# pikeyboard-56SWD2.net
KiCad netlist of a schematic drawn in EAGLE
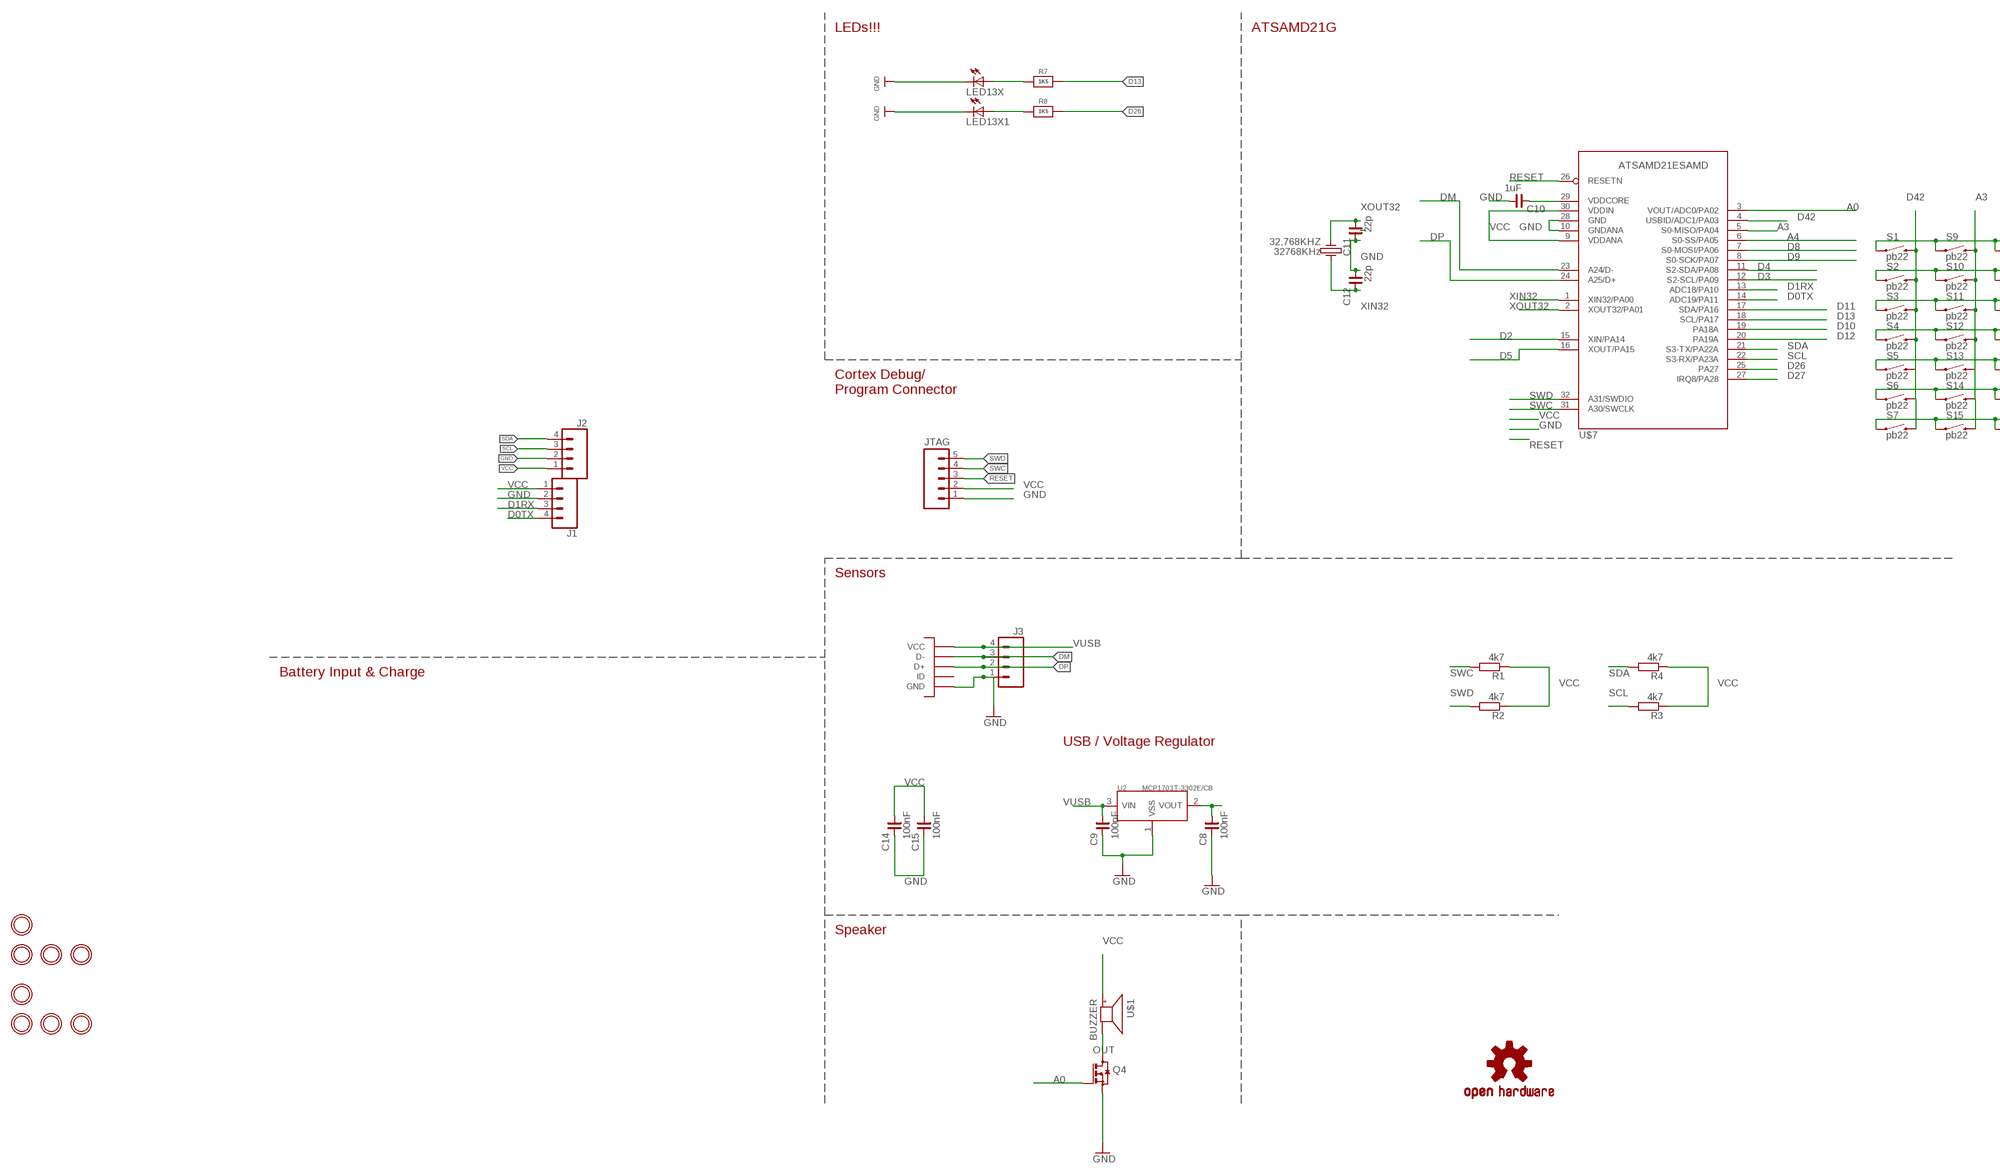
[diagram p0: schematic, sheet 1, part 1 of 2]
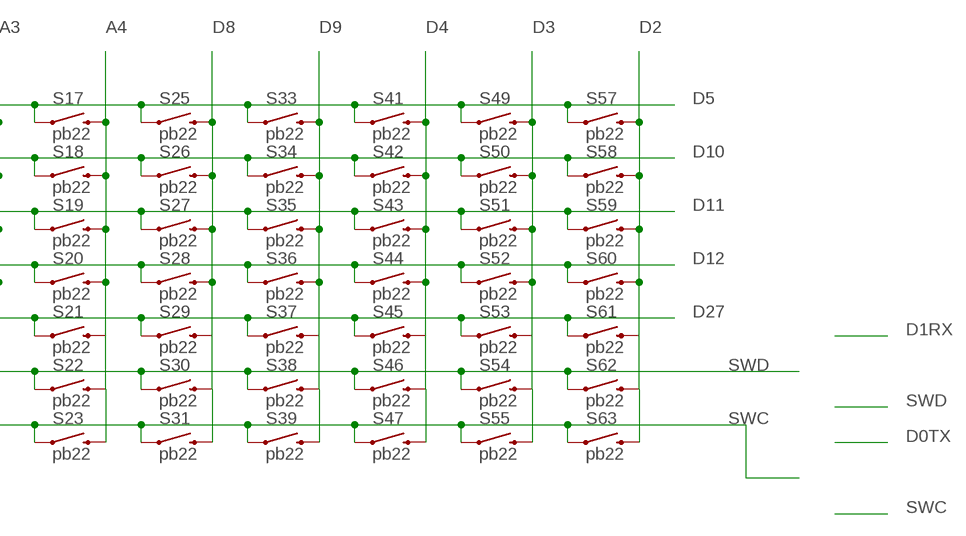
[diagram p1: schematic, sheet 1, part 2 of 2]

(export (version "E")
  (design (tool "Eeschema 10.0.6"))
  (components
    (comp (ref "32,768KHZ")
      (value "32768KHz")
      (footprint "eagle-import:KX-327LT")
      (libsource (lib "eagle-import") (part "CRYSTALL"))
    )
    (comp (ref "C8")
      (value "100nF")
      (footprint "eagle-import:C0603")
      (libsource (lib "eagle-import") (part "C_0603"))
    )
    (comp (ref "C9")
      (value "100nF")
      (footprint "eagle-import:C0603")
      (libsource (lib "eagle-import") (part "C_0603"))
    )
    (comp (ref "C10")
      (value "1uF")
      (footprint "eagle-import:C0603")
      (libsource (lib "eagle-import") (part "C_0603"))
    )
    (comp (ref "C11")
      (value "22p")
      (footprint "eagle-import:C0603")
      (libsource (lib "eagle-import") (part "C_0603"))
    )
    (comp (ref "C12")
      (value "22p")
      (footprint "eagle-import:C0603")
      (libsource (lib "eagle-import") (part "C_0603"))
    )
    (comp (ref "C14")
      (value "100nF")
      (footprint "eagle-import:C0603")
      (libsource (lib "eagle-import") (part "C_0603"))
    )
    (comp (ref "C15")
      (value "100nF")
      (footprint "eagle-import:C0603")
      (libsource (lib "eagle-import") (part "C_0603"))
    )
    (comp (ref "J1")
      (value "CONN_041X04_NO_SILK")
      (footprint "eagle-import:1X04_NO_SILK")
      (libsource (lib "eagle-import") (part "CONN_041X04_NO_SILK"))
    )
    (comp (ref "J2")
      (value "CONN_041X04_NO_SILK")
      (footprint "eagle-import:1X04_NO_SILK")
      (libsource (lib "eagle-import") (part "CONN_041X04_NO_SILK"))
    )
    (comp (ref "J3")
      (value "CONN_041.27MM")
      (footprint "eagle-import:1X04_1.27MM")
      (libsource (lib "eagle-import") (part "CONN_041.27MM"))
    )
    (comp (ref "JTAG")
      (value "M051.27MM")
      (footprint "eagle-import:1X05-1.27MM")
      (libsource (lib "eagle-import") (part "M051.27MM"))
    )
    (comp (ref "LED13X")
      (value "LED3MM")
      (footprint "eagle-import:LED3MM")
      (libsource (lib "eagle-import") (part "LED3MM"))
    )
    (comp (ref "LED13X1")
      (value "LED3MM")
      (footprint "eagle-import:LED3MM")
      (libsource (lib "eagle-import") (part "LED3MM"))
    )
    (comp (ref "LOGO3")
      (value "OSHW-LOGOS")
      (footprint "eagle-import:OSHW-LOGO-S")
      (libsource (lib "eagle-import") (part "OSHW-LOGOS"))
    )
    (comp (ref "Q4")
      (value "BSS123")
      (footprint "eagle-import:SOT23")
      (libsource (lib "eagle-import") (part "BSS123"))
    )
    (comp (ref "R1")
      (value "4k7")
      (footprint "eagle-import:R0603")
      (libsource (lib "eagle-import") (part "R-EU_R0603"))
    )
    (comp (ref "R2")
      (value "4k7")
      (footprint "eagle-import:R0603")
      (libsource (lib "eagle-import") (part "R-EU_R0603"))
    )
    (comp (ref "R3")
      (value "4k7")
      (footprint "eagle-import:R0603")
      (libsource (lib "eagle-import") (part "R-EU_R0603"))
    )
    (comp (ref "R4")
      (value "4k7")
      (footprint "eagle-import:R0603")
      (libsource (lib "eagle-import") (part "R-EU_R0603"))
    )
    (comp (ref "R7")
      (value "1K5")
      (footprint "eagle-import:0603-NO")
      (libsource (lib "eagle-import") (part "RESISTOR_0603_NOOUT"))
    )
    (comp (ref "R8")
      (value "1K5")
      (footprint "eagle-import:0603-NO")
      (libsource (lib "eagle-import") (part "RESISTOR_0603_NOOUT"))
    )
    (comp (ref "S1")
      (value "pb22")
      (footprint "eagle-import:TACTILE-PTH")
      (libsource (lib "eagle-import") (part "SWITCH-MOMENTARY-2PTH"))
    )
    (comp (ref "S2")
      (value "pb22")
      (footprint "eagle-import:TACTILE-PTH")
      (libsource (lib "eagle-import") (part "SWITCH-MOMENTARY-2PTH"))
    )
    (comp (ref "S3")
      (value "pb22")
      (footprint "eagle-import:TACTILE-PTH")
      (libsource (lib "eagle-import") (part "SWITCH-MOMENTARY-2PTH"))
    )
    (comp (ref "S4")
      (value "pb22")
      (footprint "eagle-import:TACTILE-PTH")
      (libsource (lib "eagle-import") (part "SWITCH-MOMENTARY-2PTH"))
    )
    (comp (ref "S5")
      (value "pb22")
      (footprint "eagle-import:TACTILE-PTH")
      (libsource (lib "eagle-import") (part "SWITCH-MOMENTARY-2PTH"))
    )
    (comp (ref "S6")
      (value "pb22")
      (footprint "eagle-import:TACTILE-PTH")
      (libsource (lib "eagle-import") (part "SWITCH-MOMENTARY-2PTH"))
    )
    (comp (ref "S7")
      (value "pb22")
      (footprint "eagle-import:TACTILE-PTH")
      (libsource (lib "eagle-import") (part "SWITCH-MOMENTARY-2PTH"))
    )
    (comp (ref "S9")
      (value "pb22")
      (footprint "eagle-import:TACTILE-PTH")
      (libsource (lib "eagle-import") (part "SWITCH-MOMENTARY-2PTH"))
    )
    (comp (ref "S10")
      (value "pb22")
      (footprint "eagle-import:TACTILE-PTH")
      (libsource (lib "eagle-import") (part "SWITCH-MOMENTARY-2PTH"))
    )
    (comp (ref "S11")
      (value "pb22")
      (footprint "eagle-import:TACTILE-PTH")
      (libsource (lib "eagle-import") (part "SWITCH-MOMENTARY-2PTH"))
    )
    (comp (ref "S12")
      (value "pb22")
      (footprint "eagle-import:TACTILE-PTH")
      (libsource (lib "eagle-import") (part "SWITCH-MOMENTARY-2PTH"))
    )
    (comp (ref "S13")
      (value "pb22")
      (footprint "eagle-import:TACTILE-PTH")
      (libsource (lib "eagle-import") (part "SWITCH-MOMENTARY-2PTH"))
    )
    (comp (ref "S14")
      (value "pb22")
      (footprint "eagle-import:TACTILE-PTH")
      (libsource (lib "eagle-import") (part "SWITCH-MOMENTARY-2PTH"))
    )
    (comp (ref "S15")
      (value "pb22")
      (footprint "eagle-import:TACTILE-PTH")
      (libsource (lib "eagle-import") (part "SWITCH-MOMENTARY-2PTH"))
    )
    (comp (ref "S17")
      (value "pb22")
      (footprint "eagle-import:TACTILE-PTH")
      (libsource (lib "eagle-import") (part "SWITCH-MOMENTARY-2PTH"))
    )
    (comp (ref "S18")
      (value "pb22")
      (footprint "eagle-import:TACTILE-PTH")
      (libsource (lib "eagle-import") (part "SWITCH-MOMENTARY-2PTH"))
    )
    (comp (ref "S19")
      (value "pb22")
      (footprint "eagle-import:TACTILE-PTH")
      (libsource (lib "eagle-import") (part "SWITCH-MOMENTARY-2PTH"))
    )
    (comp (ref "S20")
      (value "pb22")
      (footprint "eagle-import:TACTILE-PTH")
      (libsource (lib "eagle-import") (part "SWITCH-MOMENTARY-2PTH"))
    )
    (comp (ref "S21")
      (value "pb22")
      (footprint "eagle-import:TACTILE-PTH")
      (libsource (lib "eagle-import") (part "SWITCH-MOMENTARY-2PTH"))
    )
    (comp (ref "S22")
      (value "pb22")
      (footprint "eagle-import:TACTILE-PTH")
      (libsource (lib "eagle-import") (part "SWITCH-MOMENTARY-2PTH"))
    )
    (comp (ref "S23")
      (value "pb22")
      (footprint "eagle-import:TACTILE-PTH")
      (libsource (lib "eagle-import") (part "SWITCH-MOMENTARY-2PTH"))
    )
    (comp (ref "S25")
      (value "pb22")
      (footprint "eagle-import:TACTILE-PTH")
      (libsource (lib "eagle-import") (part "SWITCH-MOMENTARY-2PTH"))
    )
    (comp (ref "S26")
      (value "pb22")
      (footprint "eagle-import:TACTILE-PTH")
      (libsource (lib "eagle-import") (part "SWITCH-MOMENTARY-2PTH"))
    )
    (comp (ref "S27")
      (value "pb22")
      (footprint "eagle-import:TACTILE-PTH")
      (libsource (lib "eagle-import") (part "SWITCH-MOMENTARY-2PTH"))
    )
    (comp (ref "S28")
      (value "pb22")
      (footprint "eagle-import:TACTILE-PTH")
      (libsource (lib "eagle-import") (part "SWITCH-MOMENTARY-2PTH"))
    )
    (comp (ref "S29")
      (value "pb22")
      (footprint "eagle-import:TACTILE-PTH")
      (libsource (lib "eagle-import") (part "SWITCH-MOMENTARY-2PTH"))
    )
    (comp (ref "S30")
      (value "pb22")
      (footprint "eagle-import:TACTILE-PTH")
      (libsource (lib "eagle-import") (part "SWITCH-MOMENTARY-2PTH"))
    )
    (comp (ref "S31")
      (value "pb22")
      (footprint "eagle-import:TACTILE-PTH")
      (libsource (lib "eagle-import") (part "SWITCH-MOMENTARY-2PTH"))
    )
    (comp (ref "S33")
      (value "pb22")
      (footprint "eagle-import:TACTILE-PTH")
      (libsource (lib "eagle-import") (part "SWITCH-MOMENTARY-2PTH"))
    )
    (comp (ref "S34")
      (value "pb22")
      (footprint "eagle-import:TACTILE-PTH")
      (libsource (lib "eagle-import") (part "SWITCH-MOMENTARY-2PTH"))
    )
    (comp (ref "S35")
      (value "pb22")
      (footprint "eagle-import:TACTILE-PTH")
      (libsource (lib "eagle-import") (part "SWITCH-MOMENTARY-2PTH"))
    )
    (comp (ref "S36")
      (value "pb22")
      (footprint "eagle-import:TACTILE-PTH")
      (libsource (lib "eagle-import") (part "SWITCH-MOMENTARY-2PTH"))
    )
    (comp (ref "S37")
      (value "pb22")
      (footprint "eagle-import:TACTILE-PTH")
      (libsource (lib "eagle-import") (part "SWITCH-MOMENTARY-2PTH"))
    )
    (comp (ref "S38")
      (value "pb22")
      (footprint "eagle-import:TACTILE-PTH")
      (libsource (lib "eagle-import") (part "SWITCH-MOMENTARY-2PTH"))
    )
    (comp (ref "S39")
      (value "pb22")
      (footprint "eagle-import:TACTILE-PTH")
      (libsource (lib "eagle-import") (part "SWITCH-MOMENTARY-2PTH"))
    )
    (comp (ref "S41")
      (value "pb22")
      (footprint "eagle-import:TACTILE-PTH")
      (libsource (lib "eagle-import") (part "SWITCH-MOMENTARY-2PTH"))
    )
    (comp (ref "S42")
      (value "pb22")
      (footprint "eagle-import:TACTILE-PTH")
      (libsource (lib "eagle-import") (part "SWITCH-MOMENTARY-2PTH"))
    )
    (comp (ref "S43")
      (value "pb22")
      (footprint "eagle-import:TACTILE-PTH")
      (libsource (lib "eagle-import") (part "SWITCH-MOMENTARY-2PTH"))
    )
    (comp (ref "S44")
      (value "pb22")
      (footprint "eagle-import:TACTILE-PTH")
      (libsource (lib "eagle-import") (part "SWITCH-MOMENTARY-2PTH"))
    )
    (comp (ref "S45")
      (value "pb22")
      (footprint "eagle-import:TACTILE-PTH")
      (libsource (lib "eagle-import") (part "SWITCH-MOMENTARY-2PTH"))
    )
    (comp (ref "S46")
      (value "pb22")
      (footprint "eagle-import:TACTILE-PTH")
      (libsource (lib "eagle-import") (part "SWITCH-MOMENTARY-2PTH"))
    )
    (comp (ref "S47")
      (value "pb22")
      (footprint "eagle-import:TACTILE-PTH")
      (libsource (lib "eagle-import") (part "SWITCH-MOMENTARY-2PTH"))
    )
    (comp (ref "S49")
      (value "pb22")
      (footprint "eagle-import:TACTILE-PTH")
      (libsource (lib "eagle-import") (part "SWITCH-MOMENTARY-2PTH"))
    )
    (comp (ref "S50")
      (value "pb22")
      (footprint "eagle-import:TACTILE-PTH")
      (libsource (lib "eagle-import") (part "SWITCH-MOMENTARY-2PTH"))
    )
    (comp (ref "S51")
      (value "pb22")
      (footprint "eagle-import:TACTILE-PTH")
      (libsource (lib "eagle-import") (part "SWITCH-MOMENTARY-2PTH"))
    )
    (comp (ref "S52")
      (value "pb22")
      (footprint "eagle-import:TACTILE-PTH")
      (libsource (lib "eagle-import") (part "SWITCH-MOMENTARY-2PTH"))
    )
    (comp (ref "S53")
      (value "pb22")
      (footprint "eagle-import:TACTILE-PTH")
      (libsource (lib "eagle-import") (part "SWITCH-MOMENTARY-2PTH"))
    )
    (comp (ref "S54")
      (value "pb22")
      (footprint "eagle-import:TACTILE-PTH")
      (libsource (lib "eagle-import") (part "SWITCH-MOMENTARY-2PTH"))
    )
    (comp (ref "S55")
      (value "pb22")
      (footprint "eagle-import:TACTILE-PTH")
      (libsource (lib "eagle-import") (part "SWITCH-MOMENTARY-2PTH"))
    )
    (comp (ref "S57")
      (value "pb22")
      (footprint "eagle-import:TACTILE-PTH")
      (libsource (lib "eagle-import") (part "SWITCH-MOMENTARY-2PTH"))
    )
    (comp (ref "S58")
      (value "pb22")
      (footprint "eagle-import:TACTILE-PTH")
      (libsource (lib "eagle-import") (part "SWITCH-MOMENTARY-2PTH"))
    )
    (comp (ref "S59")
      (value "pb22")
      (footprint "eagle-import:TACTILE-PTH")
      (libsource (lib "eagle-import") (part "SWITCH-MOMENTARY-2PTH"))
    )
    (comp (ref "S60")
      (value "pb22")
      (footprint "eagle-import:TACTILE-PTH")
      (libsource (lib "eagle-import") (part "SWITCH-MOMENTARY-2PTH"))
    )
    (comp (ref "S61")
      (value "pb22")
      (footprint "eagle-import:TACTILE-PTH")
      (libsource (lib "eagle-import") (part "SWITCH-MOMENTARY-2PTH"))
    )
    (comp (ref "S62")
      (value "pb22")
      (footprint "eagle-import:TACTILE-PTH")
      (libsource (lib "eagle-import") (part "SWITCH-MOMENTARY-2PTH"))
    )
    (comp (ref "S63")
      (value "pb22")
      (footprint "eagle-import:TACTILE-PTH")
      (libsource (lib "eagle-import") (part "SWITCH-MOMENTARY-2PTH"))
    )
    (comp (ref "U$1")
      (value "BUZZER")
      (footprint "eagle-import:SMT-8585-BUZZER")
      (libsource (lib "eagle-import") (part "BUZZER"))
    )
    (comp (ref "U$2")
      (value "MOUNTINGHOLE2.0")
      (footprint "eagle-import:MOUNTINGHOLE_2.0_PLATED")
      (libsource (lib "eagle-import") (part "MOUNTINGHOLE2.0"))
    )
    (comp (ref "U$3")
      (value "MOUNTINGHOLE2.0")
      (footprint "eagle-import:MOUNTINGHOLE_2.0_PLATED")
      (libsource (lib "eagle-import") (part "MOUNTINGHOLE2.0"))
    )
    (comp (ref "U$4")
      (value "MOUNTINGHOLE2.0")
      (footprint "eagle-import:MOUNTINGHOLE_2.0_PLATED")
      (libsource (lib "eagle-import") (part "MOUNTINGHOLE2.0"))
    )
    (comp (ref "U$5")
      (value "MICROUSB")
      (footprint "eagle-import:MICRO_B")
      (libsource (lib "eagle-import") (part "MICROUSB"))
    )
    (comp (ref "U$7")
      (value "ATSAMD21ESAMD")
      (footprint "eagle-import:TQFP32-08")
      (libsource (lib "eagle-import") (part "ATSAMD21ESAMD"))
    )
    (comp (ref "U$8")
      (value "MOUNTINGHOLE2.0")
      (footprint "eagle-import:MOUNTINGHOLE_2.0_PLATED")
      (libsource (lib "eagle-import") (part "MOUNTINGHOLE2.0"))
    )
    (comp (ref "U$10")
      (value "MOUNTINGHOLE2.0")
      (footprint "eagle-import:MOUNTINGHOLE_2.0_PLATED")
      (libsource (lib "eagle-import") (part "MOUNTINGHOLE2.0"))
    )
    (comp (ref "U$11")
      (value "MOUNTINGHOLE2.0")
      (footprint "eagle-import:MOUNTINGHOLE_2.0_PLATED")
      (libsource (lib "eagle-import") (part "MOUNTINGHOLE2.0"))
    )
    (comp (ref "U$12")
      (value "MOUNTINGHOLE2.0")
      (footprint "eagle-import:MOUNTINGHOLE_2.0_PLATED")
      (libsource (lib "eagle-import") (part "MOUNTINGHOLE2.0"))
    )
    (comp (ref "U$13")
      (value "MOUNTINGHOLE2.0")
      (footprint "eagle-import:MOUNTINGHOLE_2.0_PLATED")
      (libsource (lib "eagle-import") (part "MOUNTINGHOLE2.0"))
    )
    (comp (ref "U2")
      (value "MCP1703T-3302E/CB")
      (footprint "eagle-import:SOT23")
      (libsource (lib "eagle-import") (part "XC6206"))
    )
  )
  (nets
    (net (code "1") (name "/A0") (class "Default")
      (node (ref "Q4") (pin "1") (pinfunction "G_1") (pintype "passive"))
      (node (ref "U$7") (pin "3") (pinfunction "VOUT/ADC0/PA02_3") (pintype "bidirectional"))
    )
    (net (code "2") (name "/A3") (class "Default")
      (node (ref "S10") (pin "3") (pinfunction "2_3") (pintype "passive"))
      (node (ref "S11") (pin "3") (pinfunction "2_3") (pintype "passive"))
      (node (ref "S12") (pin "3") (pinfunction "2_3") (pintype "passive"))
      (node (ref "S13") (pin "3") (pinfunction "2_3") (pintype "passive"))
      (node (ref "S14") (pin "3") (pinfunction "2_3") (pintype "passive"))
      (node (ref "S15") (pin "3") (pinfunction "2_3") (pintype "passive"))
      (node (ref "S9") (pin "3") (pinfunction "2_3") (pintype "passive"))
      (node (ref "U$7") (pin "5") (pinfunction "S0-MISO/PA04_5") (pintype "bidirectional"))
    )
    (net (code "3") (name "/A4") (class "Default")
      (node (ref "S17") (pin "3") (pinfunction "2_3") (pintype "passive"))
      (node (ref "S18") (pin "3") (pinfunction "2_3") (pintype "passive"))
      (node (ref "S19") (pin "3") (pinfunction "2_3") (pintype "passive"))
      (node (ref "S20") (pin "3") (pinfunction "2_3") (pintype "passive"))
      (node (ref "S21") (pin "3") (pinfunction "2_3") (pintype "passive"))
      (node (ref "S22") (pin "3") (pinfunction "2_3") (pintype "passive"))
      (node (ref "S23") (pin "3") (pinfunction "2_3") (pintype "passive"))
      (node (ref "U$7") (pin "6") (pinfunction "S0-SS/PA05_6") (pintype "bidirectional"))
    )
    (net (code "4") (name "/D0TX") (class "Default")
      (node (ref "J1") (pin "4") (pinfunction "4_4") (pintype "passive"))
      (node (ref "U$7") (pin "14") (pinfunction "ADC19/PA11_14") (pintype "bidirectional"))
    )
    (net (code "5") (name "/D1RX") (class "Default")
      (node (ref "J1") (pin "3") (pinfunction "3_3") (pintype "passive"))
      (node (ref "U$7") (pin "13") (pinfunction "ADC18/PA10_13") (pintype "bidirectional"))
    )
    (net (code "6") (name "/D2") (class "Default")
      (node (ref "S57") (pin "3") (pinfunction "2_3") (pintype "passive"))
      (node (ref "S58") (pin "3") (pinfunction "2_3") (pintype "passive"))
      (node (ref "S59") (pin "3") (pinfunction "2_3") (pintype "passive"))
      (node (ref "S60") (pin "3") (pinfunction "2_3") (pintype "passive"))
      (node (ref "S61") (pin "3") (pinfunction "2_3") (pintype "passive"))
      (node (ref "S62") (pin "3") (pinfunction "2_3") (pintype "passive"))
      (node (ref "S63") (pin "3") (pinfunction "2_3") (pintype "passive"))
      (node (ref "U$7") (pin "15") (pinfunction "XIN/PA14_15") (pintype "bidirectional"))
    )
    (net (code "7") (name "/D3") (class "Default")
      (node (ref "S49") (pin "3") (pinfunction "2_3") (pintype "passive"))
      (node (ref "S50") (pin "3") (pinfunction "2_3") (pintype "passive"))
      (node (ref "S51") (pin "3") (pinfunction "2_3") (pintype "passive"))
      (node (ref "S52") (pin "3") (pinfunction "2_3") (pintype "passive"))
      (node (ref "S53") (pin "3") (pinfunction "2_3") (pintype "passive"))
      (node (ref "S54") (pin "3") (pinfunction "2_3") (pintype "passive"))
      (node (ref "S55") (pin "3") (pinfunction "2_3") (pintype "passive"))
      (node (ref "U$7") (pin "12") (pinfunction "S2-SCL/PA09_12") (pintype "bidirectional"))
    )
    (net (code "8") (name "/D4") (class "Default")
      (node (ref "S41") (pin "3") (pinfunction "2_3") (pintype "passive"))
      (node (ref "S42") (pin "3") (pinfunction "2_3") (pintype "passive"))
      (node (ref "S43") (pin "3") (pinfunction "2_3") (pintype "passive"))
      (node (ref "S44") (pin "3") (pinfunction "2_3") (pintype "passive"))
      (node (ref "S45") (pin "3") (pinfunction "2_3") (pintype "passive"))
      (node (ref "S46") (pin "3") (pinfunction "2_3") (pintype "passive"))
      (node (ref "S47") (pin "3") (pinfunction "2_3") (pintype "passive"))
      (node (ref "U$7") (pin "11") (pinfunction "S2-SDA/PA08_11") (pintype "bidirectional"))
    )
    (net (code "9") (name "/D5") (class "Default")
      (node (ref "S1") (pin "1") (pinfunction "1_1") (pintype "passive"))
      (node (ref "S17") (pin "1") (pinfunction "1_1") (pintype "passive"))
      (node (ref "S25") (pin "1") (pinfunction "1_1") (pintype "passive"))
      (node (ref "S33") (pin "1") (pinfunction "1_1") (pintype "passive"))
      (node (ref "S41") (pin "1") (pinfunction "1_1") (pintype "passive"))
      (node (ref "S49") (pin "1") (pinfunction "1_1") (pintype "passive"))
      (node (ref "S57") (pin "1") (pinfunction "1_1") (pintype "passive"))
      (node (ref "S9") (pin "1") (pinfunction "1_1") (pintype "passive"))
      (node (ref "U$7") (pin "16") (pinfunction "XOUT/PA15_16") (pintype "bidirectional"))
    )
    (net (code "10") (name "/D8") (class "Default")
      (node (ref "S25") (pin "3") (pinfunction "2_3") (pintype "passive"))
      (node (ref "S26") (pin "3") (pinfunction "2_3") (pintype "passive"))
      (node (ref "S27") (pin "3") (pinfunction "2_3") (pintype "passive"))
      (node (ref "S28") (pin "3") (pinfunction "2_3") (pintype "passive"))
      (node (ref "S29") (pin "3") (pinfunction "2_3") (pintype "passive"))
      (node (ref "S30") (pin "3") (pinfunction "2_3") (pintype "passive"))
      (node (ref "S31") (pin "3") (pinfunction "2_3") (pintype "passive"))
      (node (ref "U$7") (pin "7") (pinfunction "S0-MOSI/PA06_7") (pintype "bidirectional"))
    )
    (net (code "11") (name "/D9") (class "Default")
      (node (ref "S33") (pin "3") (pinfunction "2_3") (pintype "passive"))
      (node (ref "S34") (pin "3") (pinfunction "2_3") (pintype "passive"))
      (node (ref "S35") (pin "3") (pinfunction "2_3") (pintype "passive"))
      (node (ref "S36") (pin "3") (pinfunction "2_3") (pintype "passive"))
      (node (ref "S37") (pin "3") (pinfunction "2_3") (pintype "passive"))
      (node (ref "S38") (pin "3") (pinfunction "2_3") (pintype "passive"))
      (node (ref "S39") (pin "3") (pinfunction "2_3") (pintype "passive"))
      (node (ref "U$7") (pin "8") (pinfunction "S0-SCK/PA07_8") (pintype "bidirectional"))
    )
    (net (code "12") (name "/D10") (class "Default")
      (node (ref "S10") (pin "1") (pinfunction "1_1") (pintype "passive"))
      (node (ref "S18") (pin "1") (pinfunction "1_1") (pintype "passive"))
      (node (ref "S2") (pin "1") (pinfunction "1_1") (pintype "passive"))
      (node (ref "S26") (pin "1") (pinfunction "1_1") (pintype "passive"))
      (node (ref "S34") (pin "1") (pinfunction "1_1") (pintype "passive"))
      (node (ref "S42") (pin "1") (pinfunction "1_1") (pintype "passive"))
      (node (ref "S50") (pin "1") (pinfunction "1_1") (pintype "passive"))
      (node (ref "S58") (pin "1") (pinfunction "1_1") (pintype "passive"))
      (node (ref "U$7") (pin "19") (pinfunction "PA18A_19") (pintype "bidirectional"))
    )
    (net (code "13") (name "/D11") (class "Default")
      (node (ref "S11") (pin "1") (pinfunction "1_1") (pintype "passive"))
      (node (ref "S19") (pin "1") (pinfunction "1_1") (pintype "passive"))
      (node (ref "S27") (pin "1") (pinfunction "1_1") (pintype "passive"))
      (node (ref "S3") (pin "1") (pinfunction "1_1") (pintype "passive"))
      (node (ref "S35") (pin "1") (pinfunction "1_1") (pintype "passive"))
      (node (ref "S43") (pin "1") (pinfunction "1_1") (pintype "passive"))
      (node (ref "S51") (pin "1") (pinfunction "1_1") (pintype "passive"))
      (node (ref "S59") (pin "1") (pinfunction "1_1") (pintype "passive"))
      (node (ref "U$7") (pin "17") (pinfunction "SDA/PA16_17") (pintype "bidirectional"))
    )
    (net (code "14") (name "/D12") (class "Default")
      (node (ref "S12") (pin "1") (pinfunction "1_1") (pintype "passive"))
      (node (ref "S20") (pin "1") (pinfunction "1_1") (pintype "passive"))
      (node (ref "S28") (pin "1") (pinfunction "1_1") (pintype "passive"))
      (node (ref "S36") (pin "1") (pinfunction "1_1") (pintype "passive"))
      (node (ref "S4") (pin "1") (pinfunction "1_1") (pintype "passive"))
      (node (ref "S44") (pin "1") (pinfunction "1_1") (pintype "passive"))
      (node (ref "S52") (pin "1") (pinfunction "1_1") (pintype "passive"))
      (node (ref "S60") (pin "1") (pinfunction "1_1") (pintype "passive"))
      (node (ref "U$7") (pin "20") (pinfunction "PA19A_20") (pintype "bidirectional"))
    )
    (net (code "15") (name "/D27") (class "Default")
      (node (ref "S13") (pin "1") (pinfunction "1_1") (pintype "passive"))
      (node (ref "S21") (pin "1") (pinfunction "1_1") (pintype "passive"))
      (node (ref "S29") (pin "1") (pinfunction "1_1") (pintype "passive"))
      (node (ref "S37") (pin "1") (pinfunction "1_1") (pintype "passive"))
      (node (ref "S45") (pin "1") (pinfunction "1_1") (pintype "passive"))
      (node (ref "S5") (pin "1") (pinfunction "1_1") (pintype "passive"))
      (node (ref "S53") (pin "1") (pinfunction "1_1") (pintype "passive"))
      (node (ref "S61") (pin "1") (pinfunction "1_1") (pintype "passive"))
      (node (ref "U$7") (pin "27") (pinfunction "IRQ8/PA28_27") (pintype "bidirectional"))
    )
    (net (code "16") (name "/D42") (class "Default")
      (node (ref "S1") (pin "3") (pinfunction "2_3") (pintype "passive"))
      (node (ref "S2") (pin "3") (pinfunction "2_3") (pintype "passive"))
      (node (ref "S3") (pin "3") (pinfunction "2_3") (pintype "passive"))
      (node (ref "S4") (pin "3") (pinfunction "2_3") (pintype "passive"))
      (node (ref "S5") (pin "3") (pinfunction "2_3") (pintype "passive"))
      (node (ref "S6") (pin "3") (pinfunction "2_3") (pintype "passive"))
      (node (ref "S7") (pin "3") (pinfunction "2_3") (pintype "passive"))
      (node (ref "U$7") (pin "4") (pinfunction "USBID/ADC1/PA03_4") (pintype "bidirectional"))
    )
    (net (code "17") (name "/OUT") (class "Default")
      (node (ref "Q4") (pin "3") (pinfunction "D_3") (pintype "passive"))
      (node (ref "U$1") (pin "-") (pinfunction "-_-") (pintype "passive"))
    )
    (net (code "18") (name "/VUSB") (class "Default")
      (node (ref "C9") (pin "1") (pinfunction "1_1") (pintype "passive"))
      (node (ref "J3") (pin "4") (pinfunction "4_4") (pintype "passive"))
      (node (ref "U$5") (pin "P1") (pinfunction "VCC_P1") (pintype "bidirectional"))
      (node (ref "U2") (pin "3") (pinfunction "VIN_3") (pintype "input"))
    )
    (net (code "19") (name "/XIN32") (class "Default")
      (node (ref "32,768KHZ") (pin "1") (pinfunction "P$1_1") (pintype "bidirectional"))
      (node (ref "C12") (pin "2") (pinfunction "2_2") (pintype "passive"))
      (node (ref "U$7") (pin "1") (pinfunction "XIN32/PA00_1") (pintype "bidirectional"))
    )
    (net (code "20") (name "/XOUT32") (class "Default")
      (node (ref "32,768KHZ") (pin "4") (pinfunction "P$2_4") (pintype "bidirectional"))
      (node (ref "C11") (pin "1") (pinfunction "1_1") (pintype "passive"))
      (node (ref "U$7") (pin "2") (pinfunction "XOUT32/PA01_2") (pintype "bidirectional"))
    )
    (net (code "21") (name "D13") (class "Default")
      (node (ref "R7") (pin "1") (pinfunction "1_1") (pintype "passive"))
      (node (ref "U$7") (pin "18") (pinfunction "SCL/PA17_18") (pintype "bidirectional"))
    )
    (net (code "22") (name "D26") (class "Default")
      (node (ref "R8") (pin "1") (pinfunction "1_1") (pintype "passive"))
      (node (ref "U$7") (pin "25") (pinfunction "PA27_25") (pintype "bidirectional"))
    )
    (net (code "23") (name "DM") (class "Default")
      (node (ref "J3") (pin "3") (pinfunction "3_3") (pintype "passive"))
      (node (ref "U$5") (pin "P2") (pinfunction "D-_P2") (pintype "bidirectional"))
      (node (ref "U$7") (pin "23") (pinfunction "A24/D-_23") (pintype "bidirectional"))
    )
    (net (code "24") (name "DP") (class "Default")
      (node (ref "J3") (pin "2") (pinfunction "2_2") (pintype "passive"))
      (node (ref "U$5") (pin "P3") (pinfunction "D+_P3") (pintype "bidirectional"))
      (node (ref "U$7") (pin "24") (pinfunction "A25/D+_24") (pintype "bidirectional"))
    )
    (net (code "25") (name "GND") (class "Default")
      (node (ref "C10") (pin "1") (pinfunction "1_1") (pintype "passive"))
      (node (ref "C11") (pin "2") (pinfunction "2_2") (pintype "passive"))
      (node (ref "C12") (pin "1") (pinfunction "1_1") (pintype "passive"))
      (node (ref "C14") (pin "2") (pinfunction "2_2") (pintype "passive"))
      (node (ref "C15") (pin "2") (pinfunction "2_2") (pintype "passive"))
      (node (ref "C8") (pin "2") (pinfunction "2_2") (pintype "passive"))
      (node (ref "C9") (pin "2") (pinfunction "2_2") (pintype "passive"))
      (node (ref "J1") (pin "2") (pinfunction "2_2") (pintype "passive"))
      (node (ref "J2") (pin "2") (pinfunction "2_2") (pintype "passive"))
      (node (ref "J3") (pin "1") (pinfunction "1_1") (pintype "passive"))
      (node (ref "JTAG") (pin "1") (pinfunction "1_1") (pintype "passive"))
      (node (ref "LED13X") (pin "K") (pinfunction "C_K") (pintype "passive"))
      (node (ref "LED13X1") (pin "K") (pinfunction "C_K") (pintype "passive"))
      (node (ref "Q4") (pin "2") (pinfunction "S_2") (pintype "passive"))
      (node (ref "U$5") (pin "GND1") (pinfunction "GND_GND1") (pintype "bidirectional"))
      (node (ref "U$5") (pin "GND2") (pinfunction "GND_GND2") (pintype "bidirectional"))
      (node (ref "U$5") (pin "GND3") (pinfunction "GND_GND3") (pintype "bidirectional"))
      (node (ref "U$5") (pin "GND4") (pinfunction "GND_GND4") (pintype "bidirectional"))
      (node (ref "U$5") (pin "GND7") (pinfunction "GND_GND7") (pintype "bidirectional"))
      (node (ref "U$5") (pin "GND8") (pinfunction "GND_GND8") (pintype "bidirectional"))
      (node (ref "U$5") (pin "P5") (pinfunction "GND_P5") (pintype "bidirectional"))
      (node (ref "U$7") (pin "10") (pinfunction "GNDANA_10") (pintype "bidirectional"))
      (node (ref "U$7") (pin "28") (pinfunction "GND_28") (pintype "bidirectional"))
      (node (ref "U2") (pin "1") (pinfunction "VSS_1") (pintype "power_in"))
    )
    (net (code "26") (name "Net-(LED13X-PadA)") (class "Default")
      (node (ref "LED13X") (pin "A") (pinfunction "A_A") (pintype "passive"))
      (node (ref "R7") (pin "2") (pinfunction "2_2") (pintype "passive"))
    )
    (net (code "27") (name "Net-(LED13X1-PadA)") (class "Default")
      (node (ref "LED13X1") (pin "A") (pinfunction "A_A") (pintype "passive"))
      (node (ref "R8") (pin "2") (pinfunction "2_2") (pintype "passive"))
    )
    (net (code "28") (name "Net-(U$7-VDDCORE)") (class "Default")
      (node (ref "C10") (pin "2") (pinfunction "2_2") (pintype "passive"))
      (node (ref "U$7") (pin "29") (pinfunction "VDDCORE_29") (pintype "bidirectional"))
    )
    (net (code "29") (name "RESET") (class "Default")
      (node (ref "JTAG") (pin "3") (pinfunction "3_3") (pintype "passive"))
      (node (ref "U$7") (pin "26") (pinfunction "RESETN_26") (pintype "bidirectional"))
    )
    (net (code "30") (name "SCL") (class "Default")
      (node (ref "J2") (pin "3") (pinfunction "3_3") (pintype "passive"))
      (node (ref "R3") (pin "2") (pinfunction "2_2") (pintype "passive"))
      (node (ref "U$7") (pin "22") (pinfunction "S3-RX/PA23A_22") (pintype "bidirectional"))
    )
    (net (code "31") (name "SDA") (class "Default")
      (node (ref "J2") (pin "4") (pinfunction "4_4") (pintype "passive"))
      (node (ref "R4") (pin "2") (pinfunction "2_2") (pintype "passive"))
      (node (ref "U$7") (pin "21") (pinfunction "S3-TX/PA22A_21") (pintype "bidirectional"))
    )
    (net (code "32") (name "SWC") (class "Default")
      (node (ref "JTAG") (pin "4") (pinfunction "4_4") (pintype "passive"))
      (node (ref "R1") (pin "2") (pinfunction "2_2") (pintype "passive"))
      (node (ref "S15") (pin "1") (pinfunction "1_1") (pintype "passive"))
      (node (ref "S23") (pin "1") (pinfunction "1_1") (pintype "passive"))
      (node (ref "S31") (pin "1") (pinfunction "1_1") (pintype "passive"))
      (node (ref "S39") (pin "1") (pinfunction "1_1") (pintype "passive"))
      (node (ref "S47") (pin "1") (pinfunction "1_1") (pintype "passive"))
      (node (ref "S55") (pin "1") (pinfunction "1_1") (pintype "passive"))
      (node (ref "S63") (pin "1") (pinfunction "1_1") (pintype "passive"))
      (node (ref "S7") (pin "1") (pinfunction "1_1") (pintype "passive"))
      (node (ref "U$7") (pin "31") (pinfunction "A30/SWCLK_31") (pintype "bidirectional"))
    )
    (net (code "33") (name "SWD") (class "Default")
      (node (ref "JTAG") (pin "5") (pinfunction "5_5") (pintype "passive"))
      (node (ref "R2") (pin "2") (pinfunction "2_2") (pintype "passive"))
      (node (ref "S14") (pin "1") (pinfunction "1_1") (pintype "passive"))
      (node (ref "S22") (pin "1") (pinfunction "1_1") (pintype "passive"))
      (node (ref "S30") (pin "1") (pinfunction "1_1") (pintype "passive"))
      (node (ref "S38") (pin "1") (pinfunction "1_1") (pintype "passive"))
      (node (ref "S46") (pin "1") (pinfunction "1_1") (pintype "passive"))
      (node (ref "S54") (pin "1") (pinfunction "1_1") (pintype "passive"))
      (node (ref "S6") (pin "1") (pinfunction "1_1") (pintype "passive"))
      (node (ref "S62") (pin "1") (pinfunction "1_1") (pintype "passive"))
      (node (ref "U$7") (pin "32") (pinfunction "A31/SWDIO_32") (pintype "bidirectional"))
    )
    (net (code "34") (name "VCC") (class "Default")
      (node (ref "C14") (pin "1") (pinfunction "1_1") (pintype "passive"))
      (node (ref "C15") (pin "1") (pinfunction "1_1") (pintype "passive"))
      (node (ref "C8") (pin "1") (pinfunction "1_1") (pintype "passive"))
      (node (ref "J1") (pin "1") (pinfunction "1_1") (pintype "passive"))
      (node (ref "J2") (pin "1") (pinfunction "1_1") (pintype "passive"))
      (node (ref "JTAG") (pin "2") (pinfunction "2_2") (pintype "passive"))
      (node (ref "R1") (pin "1") (pinfunction "1_1") (pintype "passive"))
      (node (ref "R2") (pin "1") (pinfunction "1_1") (pintype "passive"))
      (node (ref "R3") (pin "1") (pinfunction "1_1") (pintype "passive"))
      (node (ref "R4") (pin "1") (pinfunction "1_1") (pintype "passive"))
      (node (ref "U$1") (pin "+") (pinfunction "+_+") (pintype "passive"))
      (node (ref "U$7") (pin "30") (pinfunction "VDDIN_30") (pintype "bidirectional"))
      (node (ref "U$7") (pin "9") (pinfunction "VDDANA_9") (pintype "bidirectional"))
      (node (ref "U2") (pin "2") (pinfunction "VOUT_2") (pintype "output"))
    )
    (net (code "35") (name "unconnected-(U$5-ID-PadP4)") (class "Default")
      (node (ref "U$5") (pin "P4") (pinfunction "ID_P4") (pintype "bidirectional"))
    )
  )
)
